# Multivibrator.net
KiCad netlist of a schematic drawn in Altium Designer
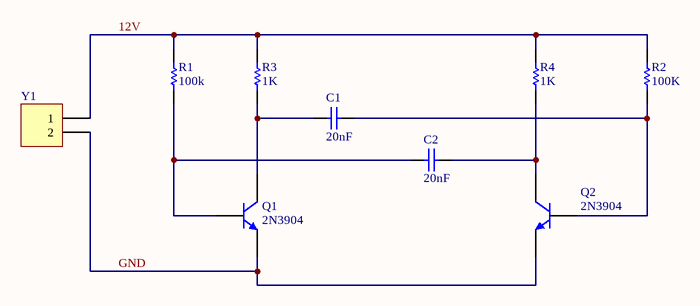
[diagram p0: Multivibrator.SchDoc]

(export (version "E")
  (design (tool "Eeschema 10.0.6"))
  (components
    (comp (ref "C1")
      (value "20nF")
      (footprint "RAD-0.3")
      (description "Capacitor")
      (fields (field (name "PUBLISHER") "Altium Limited"))
      (libsource (lib "Miscellaneous Devices") (part "Cap"))
    )
    (comp (ref "C2")
      (value "20nF")
      (footprint "RAD-0.3")
      (description "Capacitor")
      (fields (field (name "PUBLISHER") "Altium Limited"))
      (libsource (lib "Miscellaneous Devices") (part "Cap"))
    )
    (comp (ref "Q1")
      (value "2N3904")
      (footprint "TO-92A")
      (description "NPN General Purpose Amplifier")
      (fields (field (name "PUBLISHER") "Altium Limited"))
      (libsource (lib "Miscellaneous Devices") (part "2N3904"))
    )
    (comp (ref "Q2")
      (value "2N3904")
      (footprint "TO-92A")
      (description "NPN General Purpose Amplifier")
      (fields (field (name "PUBLISHER") "Altium Limited"))
      (libsource (lib "Miscellaneous Devices") (part "2N3904"))
    )
    (comp (ref "R1")
      (value "100k")
      (footprint "AXIAL-0.3")
      (description "Resistor")
      (fields (field (name "PUBLISHER") "Altium Limited"))
      (libsource (lib "Miscellaneous Devices") (part "Res1"))
    )
    (comp (ref "R2")
      (value "100K")
      (footprint "AXIAL-0.3")
      (description "Resistor")
      (fields (field (name "PUBLISHER") "Altium Limited"))
      (libsource (lib "Miscellaneous Devices") (part "Res1"))
    )
    (comp (ref "R3")
      (value "1K")
      (footprint "AXIAL-0.3")
      (description "Resistor")
      (fields (field (name "PUBLISHER") "Altium Limited"))
      (libsource (lib "Miscellaneous Devices") (part "Res1"))
    )
    (comp (ref "R4")
      (value "1K")
      (footprint "AXIAL-0.3")
      (description "Resistor")
      (fields (field (name "PUBLISHER") "Altium Limited"))
      (libsource (lib "Miscellaneous Devices") (part "Res1"))
    )
    (comp (ref "Y1")
      (value "Header 2")
      (footprint "HDR1X2")
      (description "Header, 2-Pin")
      (fields (field (name "PUBLISHER") "Altium Limited"))
      (libsource (lib "Miscellaneous Connectors") (part "Header 2"))
    )
  )
  (nets
    (net (code "1") (name "/12V") (class "Default")
      (node (ref "R1") (pin "2") (pinfunction "2_2") (pintype "passive"))
      (node (ref "R2") (pin "1") (pinfunction "1_1") (pintype "passive"))
      (node (ref "R3") (pin "1") (pinfunction "1_1") (pintype "passive"))
      (node (ref "R4") (pin "1") (pinfunction "1_1") (pintype "passive"))
      (node (ref "Y1") (pin "1") (pinfunction "1_1") (pintype "passive"))
    )
    (net (code "2") (name "/GND") (class "Default")
      (node (ref "Q1") (pin "1") (pinfunction "E_1") (pintype "passive"))
      (node (ref "Q2") (pin "1") (pinfunction "E_1") (pintype "passive"))
      (node (ref "Y1") (pin "2") (pinfunction "2_2") (pintype "passive"))
    )
    (net (code "3") (name "Net-(Q1-B)") (class "Default")
      (node (ref "C2") (pin "1") (pinfunction "1_1") (pintype "passive"))
      (node (ref "Q1") (pin "2") (pinfunction "B_2") (pintype "passive"))
      (node (ref "R1") (pin "1") (pinfunction "1_1") (pintype "passive"))
    )
    (net (code "4") (name "Net-(Q1-C)") (class "Default")
      (node (ref "C1") (pin "1") (pinfunction "1_1") (pintype "passive"))
      (node (ref "Q1") (pin "3") (pinfunction "C_3") (pintype "passive"))
      (node (ref "R3") (pin "2") (pinfunction "2_2") (pintype "passive"))
    )
    (net (code "5") (name "Net-(Q2-B)") (class "Default")
      (node (ref "C1") (pin "2") (pinfunction "2_2") (pintype "passive"))
      (node (ref "Q2") (pin "2") (pinfunction "B_2") (pintype "passive"))
      (node (ref "R2") (pin "2") (pinfunction "2_2") (pintype "passive"))
    )
    (net (code "6") (name "Net-(Q2-C)") (class "Default")
      (node (ref "C2") (pin "2") (pinfunction "2_2") (pintype "passive"))
      (node (ref "Q2") (pin "3") (pinfunction "C_3") (pintype "passive"))
      (node (ref "R4") (pin "2") (pinfunction "2_2") (pintype "passive"))
    )
  )
)
